# Sensor_Board_v1_1.net
KiCad netlist of a schematic drawn in EAGLE
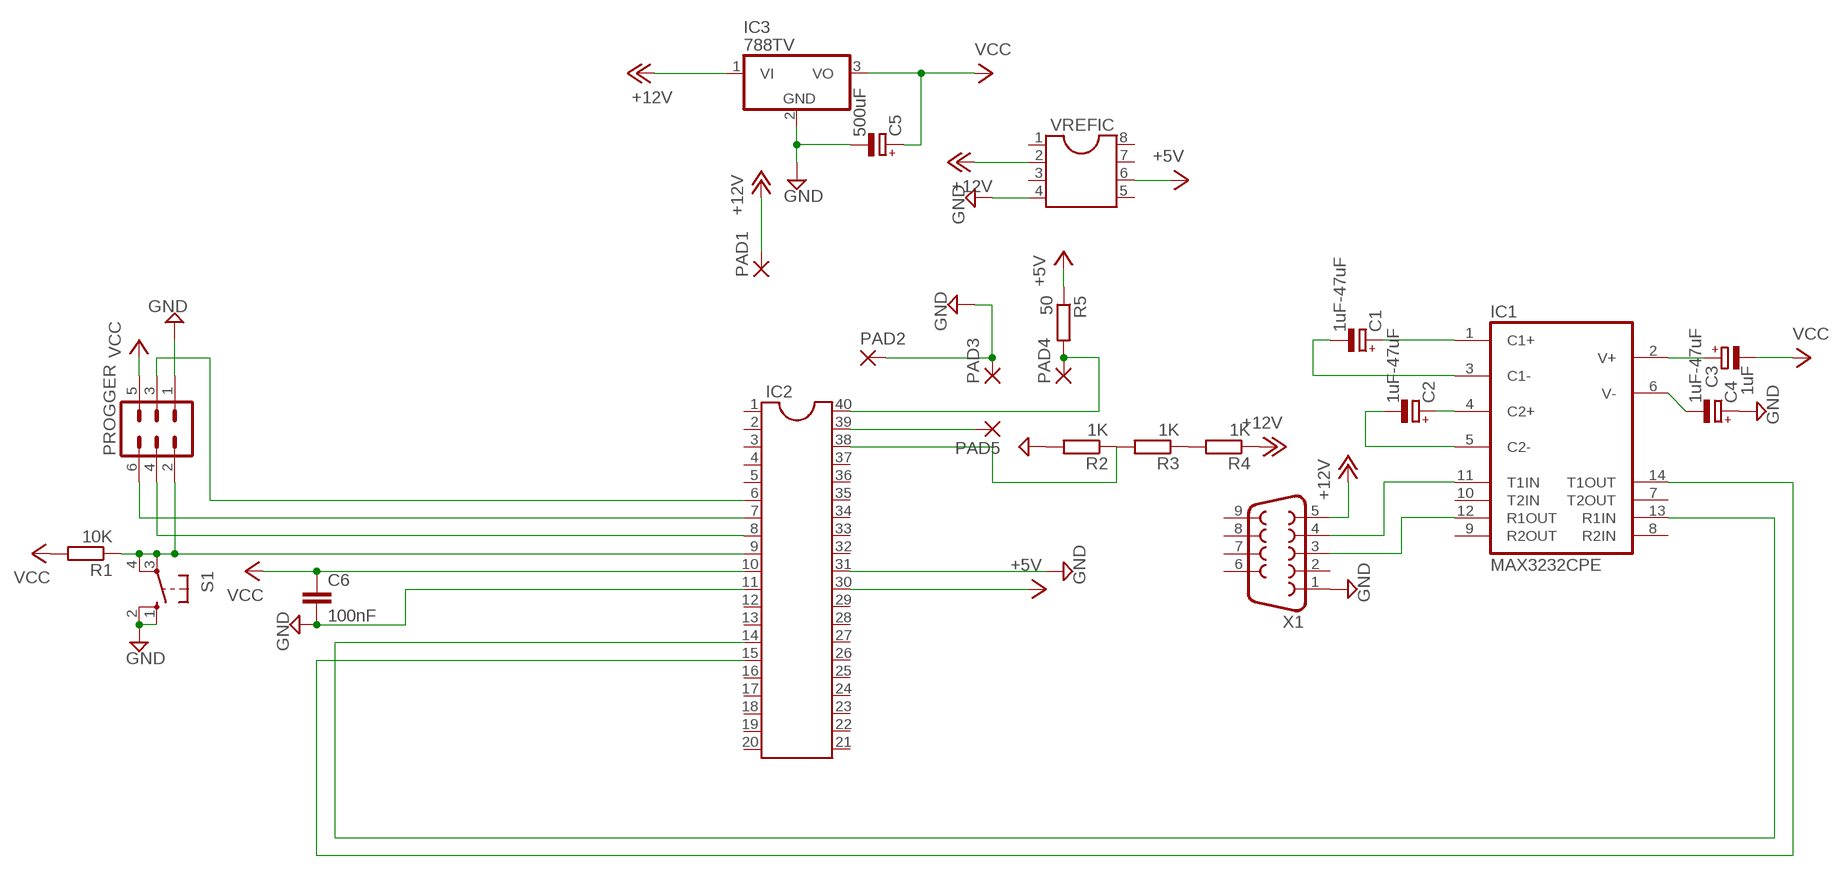
[diagram p0: schematic, sheet 1]

(export (version "E")
  (design (tool "Eeschema 10.0.6"))
  (components
    (comp (ref "C1")
      (value "1uF-47uF")
      (footprint "eagle-import:TT5D7")
      (libsource (lib "eagle-import") (part "CPOL-EUTT5D7"))
    )
    (comp (ref "C2")
      (value "1uF-47uF")
      (footprint "eagle-import:E2-4")
      (libsource (lib "eagle-import") (part "CPOL-EUE2-4"))
    )
    (comp (ref "C3")
      (value "1uF")
      (footprint "eagle-import:TT5D7")
      (libsource (lib "eagle-import") (part "CPOL-EUTT5D7"))
    )
    (comp (ref "C4")
      (value "1uF-47uF")
      (footprint "eagle-import:E2-4")
      (libsource (lib "eagle-import") (part "CPOL-EUE2-4"))
    )
    (comp (ref "C5")
      (value "500uF")
      (footprint "eagle-import:E2-4")
      (libsource (lib "eagle-import") (part "CPOL-EUE2-4"))
    )
    (comp (ref "C6")
      (value "100nF")
      (footprint "eagle-import:C025-030X050")
      (libsource (lib "eagle-import") (part "C-EU025-030X050"))
    )
    (comp (ref "IC1")
      (value "MAX3232CPE")
      (footprint "eagle-import:DIL16")
      (fields (field (name "MF") "MAXIM") (field (name "MPN") "MAX3232CPE+"))
      (libsource (lib "eagle-import") (part "MAX3232PEC"))
    )
    (comp (ref "IC2")
      (value "DIL40")
      (footprint "eagle-import:DIL40")
      (libsource (lib "eagle-import") (part "DIL40"))
    )
    (comp (ref "IC3")
      (value "788TV")
      (footprint "eagle-import:TO220V")
      (libsource (lib "eagle-import") (part "78TV8"))
    )
    (comp (ref "PAD1")
      (value "3,81/1,3")
      (footprint "eagle-import:3,81_1,3")
      (libsource (lib "eagle-import") (part "3,81/1,3"))
    )
    (comp (ref "PAD2")
      (value "3,81/1,3")
      (footprint "eagle-import:3,81_1,3")
      (libsource (lib "eagle-import") (part "3,81/1,3"))
    )
    (comp (ref "PAD3")
      (value "3,81/1,3")
      (footprint "eagle-import:3,81_1,3")
      (libsource (lib "eagle-import") (part "3,81/1,3"))
    )
    (comp (ref "PAD4")
      (value "3,81/1,3")
      (footprint "eagle-import:3,81_1,3")
      (libsource (lib "eagle-import") (part "3,81/1,3"))
    )
    (comp (ref "PAD5")
      (value "3,81/1,3")
      (footprint "eagle-import:3,81_1,3")
      (libsource (lib "eagle-import") (part "3,81/1,3"))
    )
    (comp (ref "PROGGER")
      (value "MA03-2")
      (footprint "eagle-import:MA03-2")
      (libsource (lib "eagle-import") (part "MA03-2"))
    )
    (comp (ref "R1")
      (value "10K")
      (footprint "eagle-import:0204_5")
      (libsource (lib "eagle-import") (part "R-EU_0204/5"))
    )
    (comp (ref "R2")
      (value "1K")
      (footprint "eagle-import:0204_7")
      (libsource (lib "eagle-import") (part "R-EU_0204/7"))
    )
    (comp (ref "R3")
      (value "1K")
      (footprint "eagle-import:0204_7")
      (libsource (lib "eagle-import") (part "R-EU_0204/7"))
    )
    (comp (ref "R4")
      (value "1K")
      (footprint "eagle-import:0204_7")
      (libsource (lib "eagle-import") (part "R-EU_0204/7"))
    )
    (comp (ref "R5")
      (value "50")
      (footprint "eagle-import:0204_5")
      (libsource (lib "eagle-import") (part "R-EU_0204/5"))
    )
    (comp (ref "S1")
      (value "10-XX")
      (footprint "eagle-import:B3F-10XX")
      (fields (field (name "MPN") "B3F-1000"))
      (libsource (lib "eagle-import") (part "10-XX"))
    )
    (comp (ref "VREFIC")
      (value "DIL8")
      (footprint "eagle-import:DIL08")
      (libsource (lib "eagle-import") (part "DIL8"))
    )
    (comp (ref "X1")
      (value "F09H")
      (footprint "eagle-import:F09H")
      (libsource (lib "eagle-import") (part "F09H"))
    )
  )
  (nets
    (net (code "1") (name "+5V") (class "Default")
      (node (ref "IC2") (pin "30") (pinfunction "30_30") (pintype "passive"))
      (node (ref "R5") (pin "1") (pinfunction "1_1") (pintype "passive"))
      (node (ref "VREFIC") (pin "6") (pinfunction "6_6") (pintype "passive"))
    )
    (net (code "2") (name "+12V") (class "Default")
      (node (ref "IC3") (pin "1") (pinfunction "VI_1") (pintype "input"))
      (node (ref "PAD1") (pin "1") (pinfunction "P_1") (pintype "passive"))
      (node (ref "R4") (pin "1") (pinfunction "1_1") (pintype "passive"))
      (node (ref "VREFIC") (pin "2") (pinfunction "2_2") (pintype "passive"))
      (node (ref "X1") (pin "5") (pinfunction "5_5") (pintype "passive"))
    )
    (net (code "3") (name "GND") (class "Default")
      (node (ref "C4") (pin "+") (pinfunction "+_+") (pintype "passive"))
      (node (ref "C5") (pin "-") (pinfunction "-_-") (pintype "passive"))
      (node (ref "C6") (pin "2") (pinfunction "2_2") (pintype "passive"))
      (node (ref "IC2") (pin "11") (pinfunction "11_11") (pintype "passive"))
      (node (ref "IC2") (pin "31") (pinfunction "31_31") (pintype "passive"))
      (node (ref "IC3") (pin "2") (pinfunction "GND_2") (pintype "passive"))
      (node (ref "PAD2") (pin "1") (pinfunction "P_1") (pintype "passive"))
      (node (ref "PAD3") (pin "1") (pinfunction "P_1") (pintype "passive"))
      (node (ref "PROGGER") (pin "1") (pinfunction "1_1") (pintype "passive"))
      (node (ref "R2") (pin "2") (pinfunction "2_2") (pintype "passive"))
      (node (ref "S1") (pin "1") (pinfunction "S_1") (pintype "passive"))
      (node (ref "S1") (pin "2") (pinfunction "S1_2") (pintype "passive"))
      (node (ref "VREFIC") (pin "4") (pinfunction "4_4") (pintype "passive"))
      (node (ref "X1") (pin "1") (pinfunction "1_1") (pintype "passive"))
    )
    (net (code "4") (name "Net-(IC1A-C1+)") (class "Default")
      (node (ref "C1") (pin "+") (pinfunction "+_+") (pintype "passive"))
      (node (ref "IC1") (pin "1") (pinfunction "C1+_1") (pintype "bidirectional"))
    )
    (net (code "5") (name "Net-(IC1A-C1-)") (class "Default")
      (node (ref "C1") (pin "-") (pinfunction "-_-") (pintype "passive"))
      (node (ref "IC1") (pin "3") (pinfunction "C1-_3") (pintype "bidirectional"))
    )
    (net (code "6") (name "Net-(IC1A-C2+)") (class "Default")
      (node (ref "C2") (pin "+") (pinfunction "+_+") (pintype "passive"))
      (node (ref "IC1") (pin "4") (pinfunction "C2+_4") (pintype "bidirectional"))
    )
    (net (code "7") (name "Net-(IC1A-C2-)") (class "Default")
      (node (ref "C2") (pin "-") (pinfunction "-_-") (pintype "passive"))
      (node (ref "IC1") (pin "5") (pinfunction "C2-_5") (pintype "bidirectional"))
    )
    (net (code "8") (name "Net-(IC1A-R1IN)") (class "Default")
      (node (ref "IC1") (pin "13") (pinfunction "R1IN_13") (pintype "input"))
      (node (ref "IC2") (pin "14") (pinfunction "14_14") (pintype "passive"))
    )
    (net (code "9") (name "Net-(IC1A-R1OUT)") (class "Default")
      (node (ref "IC1") (pin "12") (pinfunction "R1OUT_12") (pintype "output"))
      (node (ref "X1") (pin "3") (pinfunction "3_3") (pintype "passive"))
    )
    (net (code "10") (name "Net-(IC1A-T1IN)") (class "Default")
      (node (ref "IC1") (pin "11") (pinfunction "T1IN_11") (pintype "input"))
      (node (ref "X1") (pin "4") (pinfunction "4_4") (pintype "passive"))
    )
    (net (code "11") (name "Net-(IC1A-T1OUT)") (class "Default")
      (node (ref "IC1") (pin "14") (pinfunction "T1OUT_14") (pintype "output"))
      (node (ref "IC2") (pin "15") (pinfunction "15_15") (pintype "passive"))
    )
    (net (code "12") (name "Net-(IC1A-V+)") (class "Default")
      (node (ref "C3") (pin "+") (pinfunction "+_+") (pintype "passive"))
      (node (ref "IC1") (pin "2") (pinfunction "V+_2") (pintype "bidirectional"))
    )
    (net (code "13") (name "Net-(IC1A-V-)") (class "Default")
      (node (ref "C4") (pin "-") (pinfunction "-_-") (pintype "passive"))
      (node (ref "IC1") (pin "6") (pinfunction "V-_6") (pintype "bidirectional"))
    )
    (net (code "14") (name "Net-(IC2-Pad6)") (class "Default")
      (node (ref "IC2") (pin "6") (pinfunction "6_6") (pintype "passive"))
      (node (ref "PROGGER") (pin "3") (pinfunction "3_3") (pintype "passive"))
    )
    (net (code "15") (name "Net-(IC2-Pad7)") (class "Default")
      (node (ref "IC2") (pin "7") (pinfunction "7_7") (pintype "passive"))
      (node (ref "PROGGER") (pin "6") (pinfunction "6_6") (pintype "passive"))
    )
    (net (code "16") (name "Net-(IC2-Pad8)") (class "Default")
      (node (ref "IC2") (pin "8") (pinfunction "8_8") (pintype "passive"))
      (node (ref "PROGGER") (pin "4") (pinfunction "4_4") (pintype "passive"))
    )
    (net (code "17") (name "Net-(IC2-Pad38)") (class "Default")
      (node (ref "IC2") (pin "38") (pinfunction "38_38") (pintype "passive"))
      (node (ref "R2") (pin "1") (pinfunction "1_1") (pintype "passive"))
      (node (ref "R3") (pin "2") (pinfunction "2_2") (pintype "passive"))
    )
    (net (code "18") (name "Net-(PAD4-P)") (class "Default")
      (node (ref "IC2") (pin "40") (pinfunction "40_40") (pintype "passive"))
      (node (ref "PAD4") (pin "1") (pinfunction "P_1") (pintype "passive"))
      (node (ref "R5") (pin "2") (pinfunction "2_2") (pintype "passive"))
    )
    (net (code "19") (name "Net-(PAD5-P)") (class "Default")
      (node (ref "IC2") (pin "39") (pinfunction "39_39") (pintype "passive"))
      (node (ref "PAD5") (pin "1") (pinfunction "P_1") (pintype "passive"))
    )
    (net (code "20") (name "Net-(R3-Pad1)") (class "Default")
      (node (ref "R3") (pin "1") (pinfunction "1_1") (pintype "passive"))
      (node (ref "R4") (pin "2") (pinfunction "2_2") (pintype "passive"))
    )
    (net (code "21") (name "Net-(S1-P)") (class "Default")
      (node (ref "IC2") (pin "9") (pinfunction "9_9") (pintype "passive"))
      (node (ref "PROGGER") (pin "2") (pinfunction "2_2") (pintype "passive"))
      (node (ref "R1") (pin "1") (pinfunction "1_1") (pintype "passive"))
      (node (ref "S1") (pin "3") (pinfunction "P_3") (pintype "passive"))
      (node (ref "S1") (pin "4") (pinfunction "P1_4") (pintype "passive"))
    )
    (net (code "22") (name "VCC") (class "Default")
      (node (ref "C3") (pin "-") (pinfunction "-_-") (pintype "passive"))
      (node (ref "C5") (pin "+") (pinfunction "+_+") (pintype "passive"))
      (node (ref "C6") (pin "1") (pinfunction "1_1") (pintype "passive"))
      (node (ref "IC2") (pin "10") (pinfunction "10_10") (pintype "passive"))
      (node (ref "IC3") (pin "3") (pinfunction "VO_3") (pintype "passive"))
      (node (ref "PROGGER") (pin "5") (pinfunction "5_5") (pintype "passive"))
      (node (ref "R1") (pin "2") (pinfunction "2_2") (pintype "passive"))
    )
    (net (code "23") (name "unconnected-(IC1A-R2IN-Pad8)") (class "Default")
      (node (ref "IC1") (pin "8") (pinfunction "R2IN_8") (pintype "input"))
    )
    (net (code "24") (name "unconnected-(IC1A-R2OUT-Pad9)") (class "Default")
      (node (ref "IC1") (pin "9") (pinfunction "R2OUT_9") (pintype "output"))
    )
    (net (code "25") (name "unconnected-(IC1A-T2IN-Pad10)") (class "Default")
      (node (ref "IC1") (pin "10") (pinfunction "T2IN_10") (pintype "input"))
    )
    (net (code "26") (name "unconnected-(IC1A-T2OUT-Pad7)") (class "Default")
      (node (ref "IC1") (pin "7") (pinfunction "T2OUT_7") (pintype "output"))
    )
    (net (code "27") (name "unconnected-(IC2-Pad1)") (class "Default")
      (node (ref "IC2") (pin "1") (pinfunction "1_1") (pintype "passive"))
    )
    (net (code "28") (name "unconnected-(IC2-Pad2)") (class "Default")
      (node (ref "IC2") (pin "2") (pinfunction "2_2") (pintype "passive"))
    )
    (net (code "29") (name "unconnected-(IC2-Pad3)") (class "Default")
      (node (ref "IC2") (pin "3") (pinfunction "3_3") (pintype "passive"))
    )
    (net (code "30") (name "unconnected-(IC2-Pad4)") (class "Default")
      (node (ref "IC2") (pin "4") (pinfunction "4_4") (pintype "passive"))
    )
    (net (code "31") (name "unconnected-(IC2-Pad5)") (class "Default")
      (node (ref "IC2") (pin "5") (pinfunction "5_5") (pintype "passive"))
    )
    (net (code "32") (name "unconnected-(IC2-Pad12)") (class "Default")
      (node (ref "IC2") (pin "12") (pinfunction "12_12") (pintype "passive"))
    )
    (net (code "33") (name "unconnected-(IC2-Pad13)") (class "Default")
      (node (ref "IC2") (pin "13") (pinfunction "13_13") (pintype "passive"))
    )
    (net (code "34") (name "unconnected-(IC2-Pad16)") (class "Default")
      (node (ref "IC2") (pin "16") (pinfunction "16_16") (pintype "passive"))
    )
    (net (code "35") (name "unconnected-(IC2-Pad17)") (class "Default")
      (node (ref "IC2") (pin "17") (pinfunction "17_17") (pintype "passive"))
    )
    (net (code "36") (name "unconnected-(IC2-Pad18)") (class "Default")
      (node (ref "IC2") (pin "18") (pinfunction "18_18") (pintype "passive"))
    )
    (net (code "37") (name "unconnected-(IC2-Pad19)") (class "Default")
      (node (ref "IC2") (pin "19") (pinfunction "19_19") (pintype "passive"))
    )
    (net (code "38") (name "unconnected-(IC2-Pad20)") (class "Default")
      (node (ref "IC2") (pin "20") (pinfunction "20_20") (pintype "passive"))
    )
    (net (code "39") (name "unconnected-(IC2-Pad21)") (class "Default")
      (node (ref "IC2") (pin "21") (pinfunction "21_21") (pintype "passive"))
    )
    (net (code "40") (name "unconnected-(IC2-Pad22)") (class "Default")
      (node (ref "IC2") (pin "22") (pinfunction "22_22") (pintype "passive"))
    )
    (net (code "41") (name "unconnected-(IC2-Pad23)") (class "Default")
      (node (ref "IC2") (pin "23") (pinfunction "23_23") (pintype "passive"))
    )
    (net (code "42") (name "unconnected-(IC2-Pad24)") (class "Default")
      (node (ref "IC2") (pin "24") (pinfunction "24_24") (pintype "passive"))
    )
    (net (code "43") (name "unconnected-(IC2-Pad25)") (class "Default")
      (node (ref "IC2") (pin "25") (pinfunction "25_25") (pintype "passive"))
    )
    (net (code "44") (name "unconnected-(IC2-Pad26)") (class "Default")
      (node (ref "IC2") (pin "26") (pinfunction "26_26") (pintype "passive"))
    )
    (net (code "45") (name "unconnected-(IC2-Pad27)") (class "Default")
      (node (ref "IC2") (pin "27") (pinfunction "27_27") (pintype "passive"))
    )
    (net (code "46") (name "unconnected-(IC2-Pad28)") (class "Default")
      (node (ref "IC2") (pin "28") (pinfunction "28_28") (pintype "passive"))
    )
    (net (code "47") (name "unconnected-(IC2-Pad29)") (class "Default")
      (node (ref "IC2") (pin "29") (pinfunction "29_29") (pintype "passive"))
    )
    (net (code "48") (name "unconnected-(IC2-Pad32)") (class "Default")
      (node (ref "IC2") (pin "32") (pinfunction "32_32") (pintype "passive"))
    )
    (net (code "49") (name "unconnected-(IC2-Pad33)") (class "Default")
      (node (ref "IC2") (pin "33") (pinfunction "33_33") (pintype "passive"))
    )
    (net (code "50") (name "unconnected-(IC2-Pad34)") (class "Default")
      (node (ref "IC2") (pin "34") (pinfunction "34_34") (pintype "passive"))
    )
    (net (code "51") (name "unconnected-(IC2-Pad35)") (class "Default")
      (node (ref "IC2") (pin "35") (pinfunction "35_35") (pintype "passive"))
    )
    (net (code "52") (name "unconnected-(IC2-Pad36)") (class "Default")
      (node (ref "IC2") (pin "36") (pinfunction "36_36") (pintype "passive"))
    )
    (net (code "53") (name "unconnected-(IC2-Pad37)") (class "Default")
      (node (ref "IC2") (pin "37") (pinfunction "37_37") (pintype "passive"))
    )
    (net (code "54") (name "unconnected-(VREFIC-Pad1)") (class "Default")
      (node (ref "VREFIC") (pin "1") (pinfunction "1_1") (pintype "passive"))
    )
    (net (code "55") (name "unconnected-(VREFIC-Pad3)") (class "Default")
      (node (ref "VREFIC") (pin "3") (pinfunction "3_3") (pintype "passive"))
    )
    (net (code "56") (name "unconnected-(VREFIC-Pad5)") (class "Default")
      (node (ref "VREFIC") (pin "5") (pinfunction "5_5") (pintype "passive"))
    )
    (net (code "57") (name "unconnected-(VREFIC-Pad7)") (class "Default")
      (node (ref "VREFIC") (pin "7") (pinfunction "7_7") (pintype "passive"))
    )
    (net (code "58") (name "unconnected-(VREFIC-Pad8)") (class "Default")
      (node (ref "VREFIC") (pin "8") (pinfunction "8_8") (pintype "passive"))
    )
    (net (code "59") (name "unconnected-(X1-Pad2)") (class "Default")
      (node (ref "X1") (pin "2") (pinfunction "2_2") (pintype "passive"))
    )
    (net (code "60") (name "unconnected-(X1-Pad6)") (class "Default")
      (node (ref "X1") (pin "6") (pinfunction "6_6") (pintype "passive"))
    )
    (net (code "61") (name "unconnected-(X1-Pad7)") (class "Default")
      (node (ref "X1") (pin "7") (pinfunction "7_7") (pintype "passive"))
    )
    (net (code "62") (name "unconnected-(X1-Pad8)") (class "Default")
      (node (ref "X1") (pin "8") (pinfunction "8_8") (pintype "passive"))
    )
    (net (code "63") (name "unconnected-(X1-Pad9)") (class "Default")
      (node (ref "X1") (pin "9") (pinfunction "9_9") (pintype "passive"))
    )
  )
)
